# Servo_Controller_V2.net
KiCad netlist of a schematic drawn in EAGLE
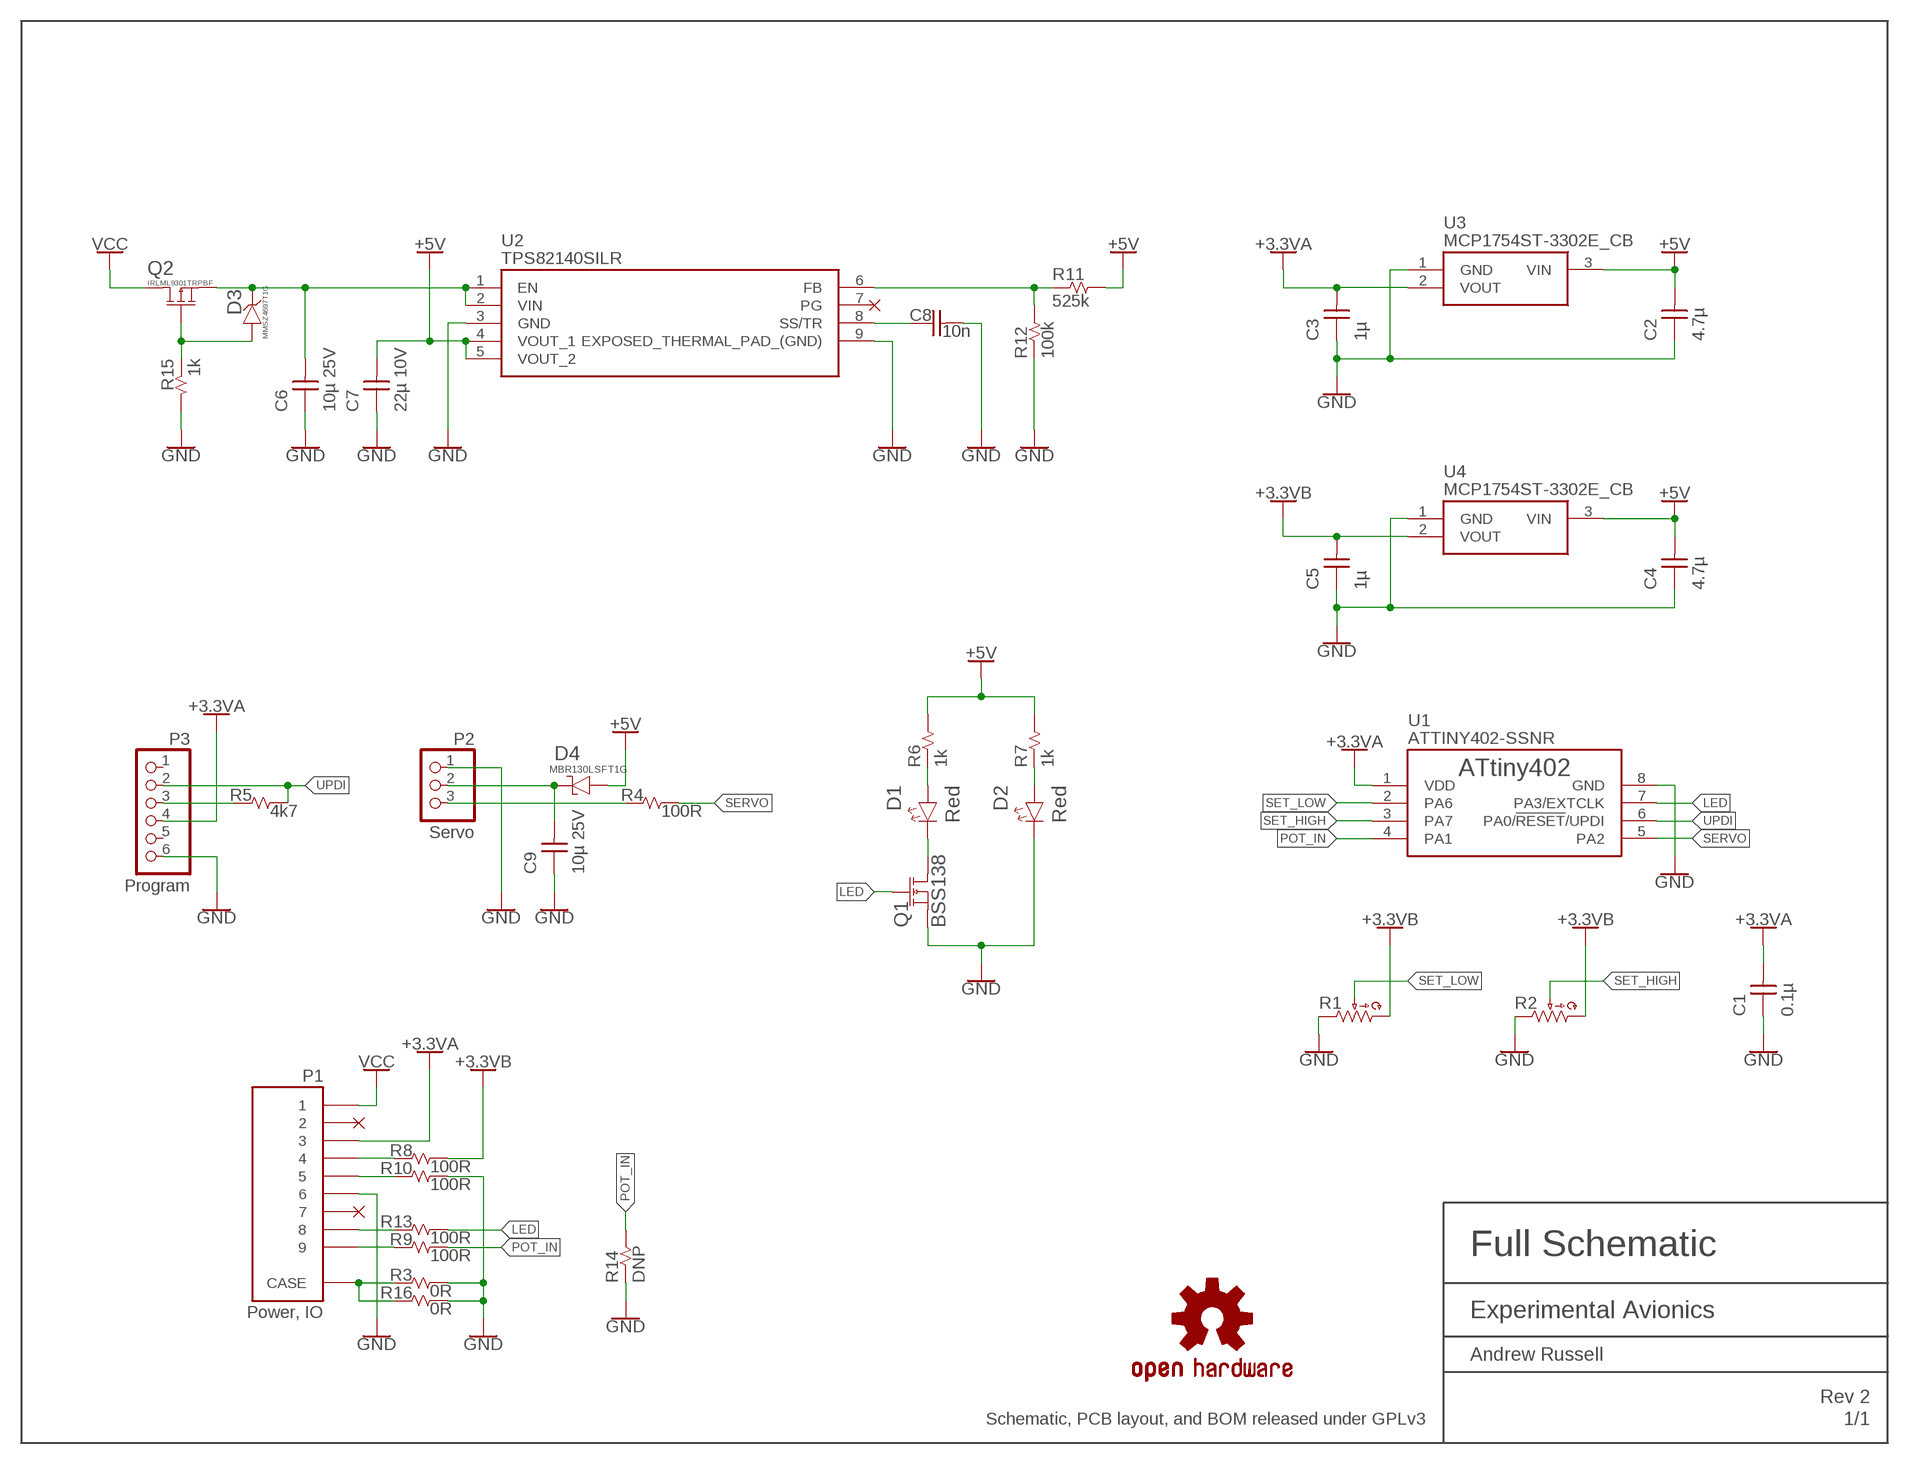
[diagram p0: schematic, sheet 1]

(export (version "E")
  (design (tool "Eeschema 10.0.6"))
  (components
    (comp (ref "C1")
      (value "0.1µ")
      (footprint "eagle-import:CAPC1608X90")
      (libsource (lib "eagle-import") (part "CAPACITOR-0603"))
    )
    (comp (ref "C2")
      (value "4.7µ")
      (footprint "eagle-import:CAPC2012X90")
      (libsource (lib "eagle-import") (part "CAPACITOR-0805"))
    )
    (comp (ref "C3")
      (value "1µ")
      (footprint "eagle-import:CAPC2012X90")
      (libsource (lib "eagle-import") (part "CAPACITOR-0805"))
    )
    (comp (ref "C4")
      (value "4.7µ")
      (footprint "eagle-import:CAPC2012X90")
      (libsource (lib "eagle-import") (part "CAPACITOR-0805"))
    )
    (comp (ref "C5")
      (value "1µ")
      (footprint "eagle-import:CAPC2012X90")
      (libsource (lib "eagle-import") (part "CAPACITOR-0805"))
    )
    (comp (ref "C6")
      (value "10µ 25V")
      (footprint "eagle-import:CAPC3216X180")
      (libsource (lib "eagle-import") (part "CAPACITOR-1206"))
    )
    (comp (ref "C7")
      (value "22µ 10V")
      (footprint "eagle-import:CAPC2012X90")
      (libsource (lib "eagle-import") (part "CAPACITOR-0805"))
    )
    (comp (ref "C8")
      (value "10n")
      (footprint "eagle-import:CAPC1608X90")
      (libsource (lib "eagle-import") (part "CAPACITOR-0603"))
    )
    (comp (ref "C9")
      (value "10µ 25V")
      (footprint "eagle-import:CAPC3216X180")
      (libsource (lib "eagle-import") (part "CAPACITOR-1206"))
    )
    (comp (ref "D1")
      (value "Red")
      (footprint "eagle-import:SODFL3216X68")
      (libsource (lib "eagle-import") (part "LED-DIALIGHT-1206"))
    )
    (comp (ref "D2")
      (value "Red")
      (footprint "eagle-import:SODFL3216X68")
      (libsource (lib "eagle-import") (part "LED-DIALIGHT-1206"))
    )
    (comp (ref "D3")
      (value "MMSZ4697T1G")
      (footprint "eagle-import:SODFL3518X115")
      (libsource (lib "eagle-import") (part "DIODE-ZENER-SOD-123F"))
    )
    (comp (ref "D4")
      (value "MBR130LSFT1G")
      (footprint "eagle-import:SODFL3616X98")
      (libsource (lib "eagle-import") (part "DIODE-SCHOTTKY-ON-MBR130LSFT1G"))
    )
    (comp (ref "LOGO1")
      (value "OSHW-LOGOMINI")
      (footprint "eagle-import:OSHW-LOGO-MINI")
      (libsource (lib "eagle-import") (part "OSHW-LOGOMINI"))
    )
    (comp (ref "P1")
      (value "Power, IO")
      (footprint "eagle-import:D09P24A4GV00LF")
      (libsource (lib "eagle-import") (part "DB9"))
    )
    (comp (ref "P2")
      (value "Servo")
      (footprint "eagle-import:1X03_90")
      (libsource (lib "eagle-import") (part "PINHD-1X3/90"))
    )
    (comp (ref "P3")
      (value "Program")
      (footprint "eagle-import:1X06")
      (libsource (lib "eagle-import") (part "PINHD-1X6"))
    )
    (comp (ref "Q1")
      (value "BSS138")
      (footprint "eagle-import:SOT95P240X110-3")
      (libsource (lib "eagle-import") (part "BSS138"))
    )
    (comp (ref "Q2")
      (value "IRLML9301TRPBF")
      (footprint "eagle-import:SOT95P240X110-3")
      (libsource (lib "eagle-import") (part "IRLML9301TRPBF"))
    )
    (comp (ref "R1")
      (value "POTENTIOMETER")
      (footprint "eagle-import:TT_23B")
      (libsource (lib "eagle-import") (part "POTENTIOMETER"))
    )
    (comp (ref "R2")
      (value "POTENTIOMETER")
      (footprint "eagle-import:TT_23B")
      (libsource (lib "eagle-import") (part "POTENTIOMETER"))
    )
    (comp (ref "R3")
      (value "0R")
      (footprint "eagle-import:RESC1608X55")
      (libsource (lib "eagle-import") (part "RESISTOR-0603"))
    )
    (comp (ref "R4")
      (value "100R")
      (footprint "eagle-import:RESC1608X55")
      (libsource (lib "eagle-import") (part "RESISTOR-0603"))
    )
    (comp (ref "R5")
      (value "4k7")
      (footprint "eagle-import:RESC1608X55")
      (libsource (lib "eagle-import") (part "RESISTOR-0603"))
    )
    (comp (ref "R6")
      (value "1k")
      (footprint "eagle-import:RESC1608X55")
      (libsource (lib "eagle-import") (part "RESISTOR-0603"))
    )
    (comp (ref "R7")
      (value "1k")
      (footprint "eagle-import:RESC1608X55")
      (libsource (lib "eagle-import") (part "RESISTOR-0603"))
    )
    (comp (ref "R8")
      (value "100R")
      (footprint "eagle-import:RESC1608X55")
      (libsource (lib "eagle-import") (part "RESISTOR-0603"))
    )
    (comp (ref "R9")
      (value "100R")
      (footprint "eagle-import:RESC1608X55")
      (libsource (lib "eagle-import") (part "RESISTOR-0603"))
    )
    (comp (ref "R10")
      (value "100R")
      (footprint "eagle-import:RESC1608X55")
      (libsource (lib "eagle-import") (part "RESISTOR-0603"))
    )
    (comp (ref "R11")
      (value "525k")
      (footprint "eagle-import:RESC1608X55")
      (libsource (lib "eagle-import") (part "RESISTOR-0603"))
    )
    (comp (ref "R12")
      (value "100k")
      (footprint "eagle-import:RESC1608X55")
      (libsource (lib "eagle-import") (part "RESISTOR-0603"))
    )
    (comp (ref "R13")
      (value "100R")
      (footprint "eagle-import:RESC1608X55")
      (libsource (lib "eagle-import") (part "RESISTOR-0603"))
    )
    (comp (ref "R14")
      (value "DNP")
      (footprint "eagle-import:RESC1608X55")
      (libsource (lib "eagle-import") (part "RESISTOR-0603"))
    )
    (comp (ref "R15")
      (value "1k")
      (footprint "eagle-import:RESC1608X55")
      (libsource (lib "eagle-import") (part "RESISTOR-0603"))
    )
    (comp (ref "R16")
      (value "0R")
      (footprint "eagle-import:RESC1608X55")
      (libsource (lib "eagle-import") (part "RESISTOR-0603"))
    )
    (comp (ref "U1")
      (value "ATTINY402-SSNR")
      (footprint "eagle-import:SOIC127P599X175-8")
      (libsource (lib "eagle-import") (part "ATTINY402-SSNR"))
    )
    (comp (ref "U2")
      (value "TPS82140SILR")
      (footprint "eagle-import:SIL0008D")
      (fields (field (name "MOUSER_PART_NUMBER") "595-TPS82140SILR"))
      (libsource (lib "eagle-import") (part "TPS82140SILR"))
    )
    (comp (ref "U3")
      (value "MCP1754ST-3302E_CB")
      (footprint "eagle-import:SOT95P255X145-3N")
      (fields
        (field (name "MANUFACTURER_PART_NUMBER") "MCP1754ST-3302E/CB")
        (field (name "MOUSER_PART_NUMBER") "579-MCP1754T-3302ECB")
        (field (name "RS_PART_NUMBER") "7559521P")
      )
      (libsource (lib "eagle-import") (part "MCP1754ST-3302E_CB"))
    )
    (comp (ref "U4")
      (value "MCP1754ST-3302E_CB")
      (footprint "eagle-import:SOT95P255X145-3N")
      (fields
        (field (name "MANUFACTURER_PART_NUMBER") "MCP1754ST-3302E/CB")
        (field (name "MOUSER_PART_NUMBER") "579-MCP1754T-3302ECB")
        (field (name "RS_PART_NUMBER") "7559521P")
      )
      (libsource (lib "eagle-import") (part "MCP1754ST-3302E_CB"))
    )
  )
  (nets
    (net (code "1") (name "+3V3A") (class "Default")
      (node (ref "C1") (pin "2") (pinfunction "P$2_2") (pintype "bidirectional"))
      (node (ref "C3") (pin "2") (pinfunction "P$2_2") (pintype "bidirectional"))
      (node (ref "P1") (pin "P$3") (pinfunction "3_P$3") (pintype "passive"))
      (node (ref "P3") (pin "4") (pinfunction "4_4") (pintype "passive"))
      (node (ref "U1") (pin "1") (pinfunction "VDD_1") (pintype "power_in"))
      (node (ref "U3") (pin "2") (pinfunction "VOUT_2") (pintype "output"))
    )
    (net (code "2") (name "+3V3B") (class "Default")
      (node (ref "C5") (pin "2") (pinfunction "P$2_2") (pintype "bidirectional"))
      (node (ref "R1") (pin "P$3") (pinfunction "P$3_P$3") (pintype "passive"))
      (node (ref "R2") (pin "P$3") (pinfunction "P$3_P$3") (pintype "passive"))
      (node (ref "R8") (pin "2") (pinfunction "P$2_2") (pintype "bidirectional"))
      (node (ref "U4") (pin "2") (pinfunction "VOUT_2") (pintype "output"))
    )
    (net (code "3") (name "+5V") (class "Default")
      (node (ref "C2") (pin "2") (pinfunction "P$2_2") (pintype "bidirectional"))
      (node (ref "C4") (pin "2") (pinfunction "P$2_2") (pintype "bidirectional"))
      (node (ref "C7") (pin "2") (pinfunction "P$2_2") (pintype "bidirectional"))
      (node (ref "D4") (pin "2") (pinfunction "A_2") (pintype "passive"))
      (node (ref "R11") (pin "2") (pinfunction "P$2_2") (pintype "bidirectional"))
      (node (ref "R6") (pin "2") (pinfunction "P$2_2") (pintype "bidirectional"))
      (node (ref "R7") (pin "2") (pinfunction "P$2_2") (pintype "bidirectional"))
      (node (ref "U2") (pin "4") (pinfunction "VOUT_1_4") (pintype "bidirectional"))
      (node (ref "U2") (pin "5") (pinfunction "VOUT_2_5") (pintype "bidirectional"))
      (node (ref "U3") (pin "3") (pinfunction "VIN_3") (pintype "input"))
      (node (ref "U4") (pin "3") (pinfunction "VIN_3") (pintype "input"))
    )
    (net (code "4") (name "GND") (class "Default")
      (node (ref "C1") (pin "1") (pinfunction "P$1_1") (pintype "bidirectional"))
      (node (ref "C2") (pin "1") (pinfunction "P$1_1") (pintype "bidirectional"))
      (node (ref "C3") (pin "1") (pinfunction "P$1_1") (pintype "bidirectional"))
      (node (ref "C4") (pin "1") (pinfunction "P$1_1") (pintype "bidirectional"))
      (node (ref "C5") (pin "1") (pinfunction "P$1_1") (pintype "bidirectional"))
      (node (ref "C6") (pin "1") (pinfunction "P$1_1") (pintype "bidirectional"))
      (node (ref "C7") (pin "1") (pinfunction "P$1_1") (pintype "bidirectional"))
      (node (ref "C8") (pin "2") (pinfunction "P$2_2") (pintype "bidirectional"))
      (node (ref "C9") (pin "1") (pinfunction "P$1_1") (pintype "bidirectional"))
      (node (ref "D2") (pin "1") (pinfunction "C_1") (pintype "passive"))
      (node (ref "P1") (pin "P$6") (pinfunction "6_P$6") (pintype "passive"))
      (node (ref "P2") (pin "1") (pinfunction "1_1") (pintype "passive"))
      (node (ref "P3") (pin "6") (pinfunction "6_6") (pintype "passive"))
      (node (ref "Q1") (pin "2") (pinfunction "S_2") (pintype "bidirectional"))
      (node (ref "R1") (pin "P$1") (pinfunction "P$1_P$1") (pintype "passive"))
      (node (ref "R10") (pin "2") (pinfunction "P$2_2") (pintype "bidirectional"))
      (node (ref "R12") (pin "1") (pinfunction "P$1_1") (pintype "bidirectional"))
      (node (ref "R14") (pin "1") (pinfunction "P$1_1") (pintype "bidirectional"))
      (node (ref "R15") (pin "2") (pinfunction "P$2_2") (pintype "bidirectional"))
      (node (ref "R16") (pin "2") (pinfunction "P$2_2") (pintype "bidirectional"))
      (node (ref "R2") (pin "P$1") (pinfunction "P$1_P$1") (pintype "passive"))
      (node (ref "R3") (pin "2") (pinfunction "P$2_2") (pintype "bidirectional"))
      (node (ref "U1") (pin "8") (pinfunction "GND_8") (pintype "power_in"))
      (node (ref "U2") (pin "3") (pinfunction "GND_3") (pintype "bidirectional"))
      (node (ref "U2") (pin "9") (pinfunction "EXPOSED_THERMAL_PAD_(GND)_9") (pintype "bidirectional"))
      (node (ref "U3") (pin "1") (pinfunction "GND_1") (pintype "power_in"))
      (node (ref "U4") (pin "1") (pinfunction "GND_1") (pintype "power_in"))
    )
    (net (code "5") (name "LED") (class "Default")
      (node (ref "Q1") (pin "1") (pinfunction "G_1") (pintype "bidirectional"))
      (node (ref "R13") (pin "2") (pinfunction "P$2_2") (pintype "bidirectional"))
      (node (ref "U1") (pin "7") (pinfunction "PA3/EXTCLK_7") (pintype "bidirectional"))
    )
    (net (code "6") (name "Net-(C6-P$2)") (class "Default")
      (node (ref "C6") (pin "2") (pinfunction "P$2_2") (pintype "bidirectional"))
      (node (ref "D3") (pin "1") (pinfunction "C_1") (pintype "passive"))
      (node (ref "Q2") (pin "2") (pinfunction "S_2") (pintype "bidirectional"))
      (node (ref "U2") (pin "1") (pinfunction "EN_1") (pintype "bidirectional"))
      (node (ref "U2") (pin "2") (pinfunction "VIN_2") (pintype "bidirectional"))
    )
    (net (code "7") (name "Net-(C8-P$1)") (class "Default")
      (node (ref "C8") (pin "1") (pinfunction "P$1_1") (pintype "bidirectional"))
      (node (ref "U2") (pin "8") (pinfunction "SS/TR_8") (pintype "bidirectional"))
    )
    (net (code "8") (name "Net-(C9-P$2)") (class "Default")
      (node (ref "C9") (pin "2") (pinfunction "P$2_2") (pintype "bidirectional"))
      (node (ref "D4") (pin "1") (pinfunction "C_1") (pintype "passive"))
      (node (ref "P2") (pin "2") (pinfunction "2_2") (pintype "passive"))
    )
    (net (code "9") (name "Net-(D1-A)") (class "Default")
      (node (ref "D1") (pin "2") (pinfunction "A_2") (pintype "passive"))
      (node (ref "R6") (pin "1") (pinfunction "P$1_1") (pintype "bidirectional"))
    )
    (net (code "10") (name "Net-(D1-C)") (class "Default")
      (node (ref "D1") (pin "1") (pinfunction "C_1") (pintype "passive"))
      (node (ref "Q1") (pin "3") (pinfunction "D_3") (pintype "bidirectional"))
    )
    (net (code "11") (name "Net-(D2-A)") (class "Default")
      (node (ref "D2") (pin "2") (pinfunction "A_2") (pintype "passive"))
      (node (ref "R7") (pin "1") (pinfunction "P$1_1") (pintype "bidirectional"))
    )
    (net (code "12") (name "Net-(D3-A)") (class "Default")
      (node (ref "D3") (pin "2") (pinfunction "A_2") (pintype "passive"))
      (node (ref "Q2") (pin "1") (pinfunction "G_1") (pintype "bidirectional"))
      (node (ref "R15") (pin "1") (pinfunction "P$1_1") (pintype "bidirectional"))
    )
    (net (code "13") (name "Net-(P1-4)") (class "Default")
      (node (ref "P1") (pin "P$4") (pinfunction "4_P$4") (pintype "passive"))
      (node (ref "R8") (pin "1") (pinfunction "P$1_1") (pintype "bidirectional"))
    )
    (net (code "14") (name "Net-(P1-5)") (class "Default")
      (node (ref "P1") (pin "P$5") (pinfunction "5_P$5") (pintype "passive"))
      (node (ref "R10") (pin "1") (pinfunction "P$1_1") (pintype "bidirectional"))
    )
    (net (code "15") (name "Net-(P1-8)") (class "Default")
      (node (ref "P1") (pin "P$8") (pinfunction "8_P$8") (pintype "passive"))
      (node (ref "R13") (pin "1") (pinfunction "P$1_1") (pintype "bidirectional"))
    )
    (net (code "16") (name "Net-(P1-9)") (class "Default")
      (node (ref "P1") (pin "P$9") (pinfunction "9_P$9") (pintype "passive"))
      (node (ref "R9") (pin "1") (pinfunction "P$1_1") (pintype "bidirectional"))
    )
    (net (code "17") (name "Net-(R4-P$1)") (class "Default")
      (node (ref "P2") (pin "3") (pinfunction "3_3") (pintype "passive"))
      (node (ref "R4") (pin "1") (pinfunction "P$1_1") (pintype "bidirectional"))
    )
    (net (code "18") (name "Net-(R5-P$1)") (class "Default")
      (node (ref "P3") (pin "3") (pinfunction "3_3") (pintype "passive"))
      (node (ref "R5") (pin "1") (pinfunction "P$1_1") (pintype "bidirectional"))
    )
    (net (code "19") (name "Net-(R11-P$1)") (class "Default")
      (node (ref "R11") (pin "1") (pinfunction "P$1_1") (pintype "bidirectional"))
      (node (ref "R12") (pin "2") (pinfunction "P$2_2") (pintype "bidirectional"))
      (node (ref "U2") (pin "6") (pinfunction "FB_6") (pintype "bidirectional"))
    )
    (net (code "20") (name "Net-(R16-P$1)") (class "Default")
      (node (ref "P1") (pin "P$10") (pinfunction "CASE_P$10") (pintype "passive"))
      (node (ref "P1") (pin "P$11") (pinfunction "CASE_P$11") (pintype "passive"))
      (node (ref "R16") (pin "1") (pinfunction "P$1_1") (pintype "bidirectional"))
      (node (ref "R3") (pin "1") (pinfunction "P$1_1") (pintype "bidirectional"))
    )
    (net (code "21") (name "POT_IN") (class "Default")
      (node (ref "R14") (pin "2") (pinfunction "P$2_2") (pintype "bidirectional"))
      (node (ref "R9") (pin "2") (pinfunction "P$2_2") (pintype "bidirectional"))
      (node (ref "U1") (pin "4") (pinfunction "PA1_4") (pintype "bidirectional"))
    )
    (net (code "22") (name "SERVO") (class "Default")
      (node (ref "R4") (pin "2") (pinfunction "P$2_2") (pintype "bidirectional"))
      (node (ref "U1") (pin "5") (pinfunction "PA2_5") (pintype "bidirectional"))
    )
    (net (code "23") (name "SET_HIGH") (class "Default")
      (node (ref "R2") (pin "P$2") (pinfunction "P$2_P$2") (pintype "passive"))
      (node (ref "U1") (pin "3") (pinfunction "PA7_3") (pintype "bidirectional"))
    )
    (net (code "24") (name "SET_LOW") (class "Default")
      (node (ref "R1") (pin "P$2") (pinfunction "P$2_P$2") (pintype "passive"))
      (node (ref "U1") (pin "2") (pinfunction "PA6_2") (pintype "bidirectional"))
    )
    (net (code "25") (name "UPDI") (class "Default")
      (node (ref "P3") (pin "2") (pinfunction "2_2") (pintype "passive"))
      (node (ref "R5") (pin "2") (pinfunction "P$2_2") (pintype "bidirectional"))
      (node (ref "U1") (pin "6") (pinfunction "PA0/~{RESET}/UPDI_6") (pintype "bidirectional"))
    )
    (net (code "26") (name "VCC") (class "Default")
      (node (ref "P1") (pin "P$1") (pinfunction "1_P$1") (pintype "passive"))
      (node (ref "Q2") (pin "3") (pinfunction "D_3") (pintype "bidirectional"))
    )
    (net (code "27") (name "unconnected-(P1-2-PadP$2)") (class "Default")
      (node (ref "P1") (pin "P$2") (pinfunction "2_P$2") (pintype "passive"))
    )
    (net (code "28") (name "unconnected-(P1-7-PadP$7)") (class "Default")
      (node (ref "P1") (pin "P$7") (pinfunction "7_P$7") (pintype "passive"))
    )
    (net (code "29") (name "unconnected-(P3-Pad1)") (class "Default")
      (node (ref "P3") (pin "1") (pinfunction "1_1") (pintype "passive"))
    )
    (net (code "30") (name "unconnected-(P3-Pad5)") (class "Default")
      (node (ref "P3") (pin "5") (pinfunction "5_5") (pintype "passive"))
    )
    (net (code "31") (name "unconnected-(U2-PG-Pad7)") (class "Default")
      (node (ref "U2") (pin "7") (pinfunction "PG_7") (pintype "bidirectional"))
    )
  )
)
